# eNode4.net
KiCad netlist of a schematic drawn in EAGLE
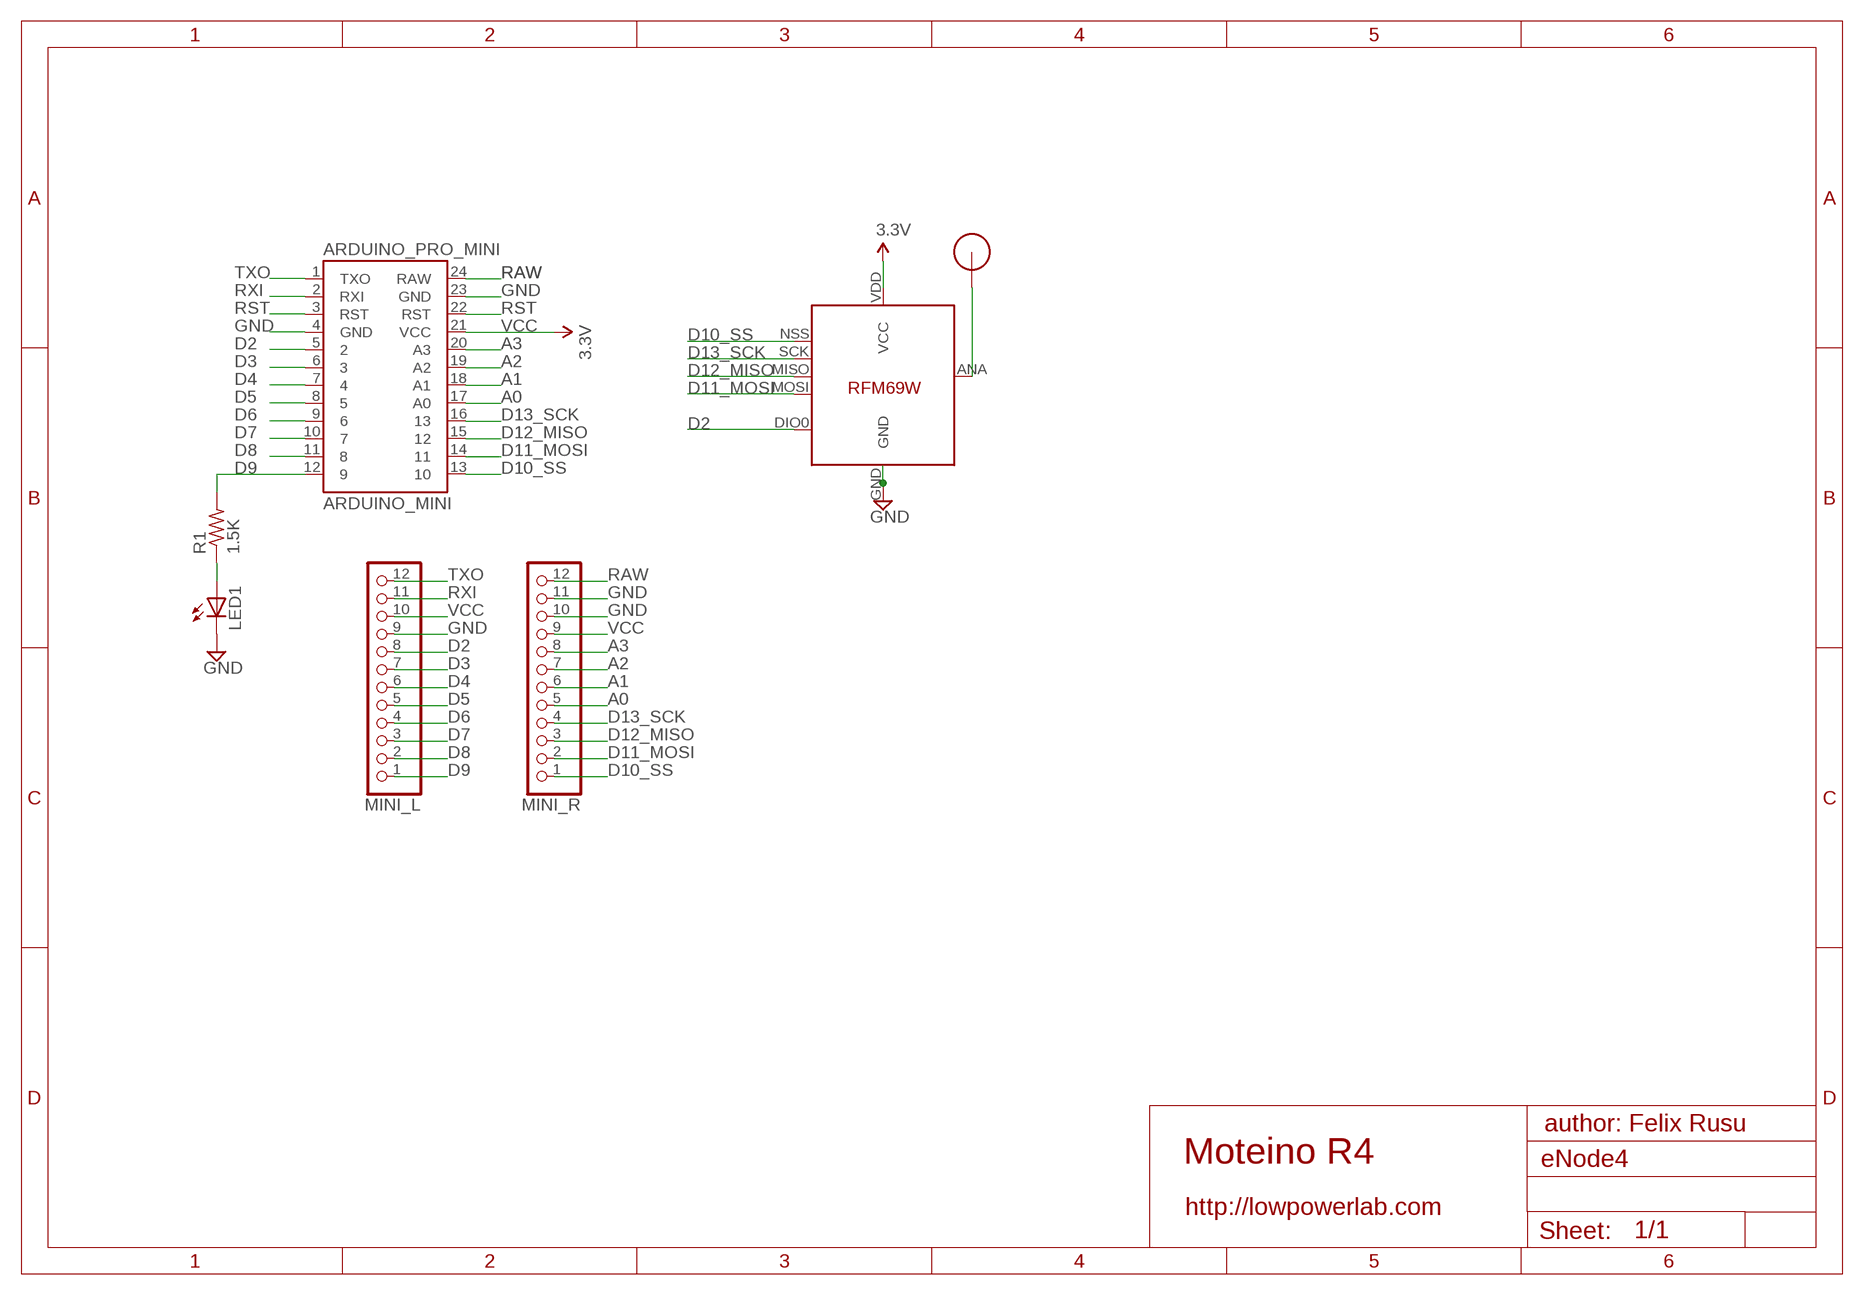
[diagram p0: schematic, sheet 1]

(export (version "E")
  (design (tool "Eeschema 10.0.6"))
  (components
    (comp (ref "ARDUINO_PRO_MINI")
      (value "ARDUINO_MINI")
      (footprint "eagle-import:ARDUINO_MINI")
      (libsource (lib "eagle-import") (part "ARDUINO_MINI"))
    )
    (comp (ref "LED1")
      (value "LED3MM")
      (footprint "eagle-import:LED3MM")
      (libsource (lib "eagle-import") (part "LED3MM"))
    )
    (comp (ref "MINI_L")
      (value "PINHD-1X12-CB")
      (footprint "eagle-import:1X12-CB")
      (libsource (lib "eagle-import") (part "PINHD-1X12-CB"))
    )
    (comp (ref "MINI_R")
      (value "PINHD-1X12-CB")
      (footprint "eagle-import:1X12-CB")
      (libsource (lib "eagle-import") (part "PINHD-1X12-CB"))
    )
    (comp (ref "R1")
      (value "1.5K")
      (footprint "eagle-import:R0805")
      (libsource (lib "eagle-import") (part "R-US_R0805"))
    )
    (comp (ref "U$1")
      (value "RFM12B_ANTENNA")
      (footprint "eagle-import:RFM12B-ANTENNA")
      (libsource (lib "eagle-import") (part "RFM12B_ANTENNA"))
    )
    (comp (ref "U$5")
      (value "RFM69")
      (footprint "eagle-import:RFM69W-MINPADS")
      (libsource (lib "eagle-import") (part "RFM69"))
    )
  )
  (nets
    (net (code "1") (name "/A0") (class "Default")
      (node (ref "ARDUINO_PRO_MINI") (pin "17") (pinfunction "A0_17") (pintype "bidirectional"))
      (node (ref "MINI_R") (pin "5") (pinfunction "5_5") (pintype "passive"))
    )
    (net (code "2") (name "/A1") (class "Default")
      (node (ref "ARDUINO_PRO_MINI") (pin "18") (pinfunction "A1_18") (pintype "bidirectional"))
      (node (ref "MINI_R") (pin "6") (pinfunction "6_6") (pintype "passive"))
    )
    (net (code "3") (name "/A2") (class "Default")
      (node (ref "ARDUINO_PRO_MINI") (pin "19") (pinfunction "A2_19") (pintype "bidirectional"))
      (node (ref "MINI_R") (pin "7") (pinfunction "7_7") (pintype "passive"))
    )
    (net (code "4") (name "/A3") (class "Default")
      (node (ref "ARDUINO_PRO_MINI") (pin "20") (pinfunction "A3_20") (pintype "bidirectional"))
      (node (ref "MINI_R") (pin "8") (pinfunction "8_8") (pintype "passive"))
    )
    (net (code "5") (name "/D2") (class "Default")
      (node (ref "ARDUINO_PRO_MINI") (pin "5") (pinfunction "2_5") (pintype "bidirectional"))
      (node (ref "MINI_L") (pin "8") (pinfunction "8_8") (pintype "passive"))
      (node (ref "U$5") (pin "DIO0") (pinfunction "DIO0_DIO0") (pintype "open_collector"))
    )
    (net (code "6") (name "/D3") (class "Default")
      (node (ref "ARDUINO_PRO_MINI") (pin "6") (pinfunction "3_6") (pintype "bidirectional"))
      (node (ref "MINI_L") (pin "7") (pinfunction "7_7") (pintype "passive"))
    )
    (net (code "7") (name "/D4") (class "Default")
      (node (ref "ARDUINO_PRO_MINI") (pin "7") (pinfunction "4_7") (pintype "bidirectional"))
      (node (ref "MINI_L") (pin "6") (pinfunction "6_6") (pintype "passive"))
    )
    (net (code "8") (name "/D5") (class "Default")
      (node (ref "ARDUINO_PRO_MINI") (pin "8") (pinfunction "5_8") (pintype "bidirectional"))
      (node (ref "MINI_L") (pin "5") (pinfunction "5_5") (pintype "passive"))
    )
    (net (code "9") (name "/D6") (class "Default")
      (node (ref "ARDUINO_PRO_MINI") (pin "9") (pinfunction "6_9") (pintype "bidirectional"))
      (node (ref "MINI_L") (pin "4") (pinfunction "4_4") (pintype "passive"))
    )
    (net (code "10") (name "/D7") (class "Default")
      (node (ref "ARDUINO_PRO_MINI") (pin "10") (pinfunction "7_10") (pintype "bidirectional"))
      (node (ref "MINI_L") (pin "3") (pinfunction "3_3") (pintype "passive"))
    )
    (net (code "11") (name "/D8") (class "Default")
      (node (ref "ARDUINO_PRO_MINI") (pin "11") (pinfunction "8_11") (pintype "bidirectional"))
      (node (ref "MINI_L") (pin "2") (pinfunction "2_2") (pintype "passive"))
    )
    (net (code "12") (name "/D9") (class "Default")
      (node (ref "ARDUINO_PRO_MINI") (pin "12") (pinfunction "9_12") (pintype "bidirectional"))
      (node (ref "MINI_L") (pin "1") (pinfunction "1_1") (pintype "passive"))
      (node (ref "R1") (pin "2") (pinfunction "2_2") (pintype "passive"))
    )
    (net (code "13") (name "/D10_SS") (class "Default")
      (node (ref "ARDUINO_PRO_MINI") (pin "13") (pinfunction "10_13") (pintype "bidirectional"))
      (node (ref "MINI_R") (pin "1") (pinfunction "1_1") (pintype "passive"))
      (node (ref "U$5") (pin "NSS") (pinfunction "SEL_NSS") (pintype "input"))
    )
    (net (code "14") (name "/D11_MOSI") (class "Default")
      (node (ref "ARDUINO_PRO_MINI") (pin "14") (pinfunction "11_14") (pintype "bidirectional"))
      (node (ref "MINI_R") (pin "2") (pinfunction "2_2") (pintype "passive"))
      (node (ref "U$5") (pin "MOSI") (pinfunction "MOSI_MOSI") (pintype "output"))
    )
    (net (code "15") (name "/D12_MISO") (class "Default")
      (node (ref "ARDUINO_PRO_MINI") (pin "15") (pinfunction "12_15") (pintype "bidirectional"))
      (node (ref "MINI_R") (pin "3") (pinfunction "3_3") (pintype "passive"))
      (node (ref "U$5") (pin "MISO") (pinfunction "MISO_MISO") (pintype "input"))
    )
    (net (code "16") (name "/D13_SCK") (class "Default")
      (node (ref "ARDUINO_PRO_MINI") (pin "16") (pinfunction "13_16") (pintype "bidirectional"))
      (node (ref "MINI_R") (pin "4") (pinfunction "4_4") (pintype "passive"))
      (node (ref "U$5") (pin "SCK") (pinfunction "SCK_SCK") (pintype "input"))
    )
    (net (code "17") (name "/RAW") (class "Default")
      (node (ref "ARDUINO_PRO_MINI") (pin "24") (pinfunction "RAW_24") (pintype "bidirectional"))
      (node (ref "MINI_R") (pin "12") (pinfunction "12_12") (pintype "passive"))
    )
    (net (code "18") (name "/RST") (class "Default")
      (node (ref "ARDUINO_PRO_MINI") (pin "22") (pinfunction "RST_22") (pintype "bidirectional"))
      (node (ref "ARDUINO_PRO_MINI") (pin "3") (pinfunction "RST_3") (pintype "bidirectional"))
    )
    (net (code "19") (name "/RXI") (class "Default")
      (node (ref "ARDUINO_PRO_MINI") (pin "2") (pinfunction "RXI_2") (pintype "bidirectional"))
      (node (ref "MINI_L") (pin "11") (pinfunction "11_11") (pintype "passive"))
    )
    (net (code "20") (name "/TXO") (class "Default")
      (node (ref "ARDUINO_PRO_MINI") (pin "1") (pinfunction "TXO_1") (pintype "bidirectional"))
      (node (ref "MINI_L") (pin "12") (pinfunction "12_12") (pintype "passive"))
    )
    (net (code "21") (name "3.3V") (class "Default")
      (node (ref "ARDUINO_PRO_MINI") (pin "21") (pinfunction "VCC_21") (pintype "bidirectional"))
      (node (ref "MINI_L") (pin "10") (pinfunction "10_10") (pintype "passive"))
      (node (ref "MINI_R") (pin "9") (pinfunction "9_9") (pintype "passive"))
      (node (ref "U$5") (pin "VDD") (pinfunction "VCC_VDD") (pintype "power_in"))
    )
    (net (code "22") (name "GND") (class "Default")
      (node (ref "ARDUINO_PRO_MINI") (pin "23") (pinfunction "GND_23") (pintype "bidirectional"))
      (node (ref "ARDUINO_PRO_MINI") (pin "4") (pinfunction "GND_4") (pintype "bidirectional"))
      (node (ref "LED1") (pin "K") (pinfunction "C_K") (pintype "passive"))
      (node (ref "MINI_L") (pin "9") (pinfunction "9_9") (pintype "passive"))
      (node (ref "MINI_R") (pin "10") (pinfunction "10_10") (pintype "passive"))
      (node (ref "MINI_R") (pin "11") (pinfunction "11_11") (pintype "passive"))
      (node (ref "U$5") (pin "GND") (pinfunction "GND_GND") (pintype "power_in"))
    )
    (net (code "23") (name "Net-(LED1-PadA)") (class "Default")
      (node (ref "LED1") (pin "A") (pinfunction "A_A") (pintype "passive"))
      (node (ref "R1") (pin "1") (pinfunction "1_1") (pintype "passive"))
    )
    (net (code "24") (name "Net-(U$1-1)") (class "Default")
      (node (ref "U$1") (pin "P$1") (pinfunction "1_P$1") (pintype "bidirectional"))
      (node (ref "U$5") (pin "ANA") (pinfunction "ANT_ANA") (pintype "passive"))
    )
  )
)
